# slim_bus_mixer_v1-4-layer.net
KiCad netlist of a schematic drawn in EAGLE
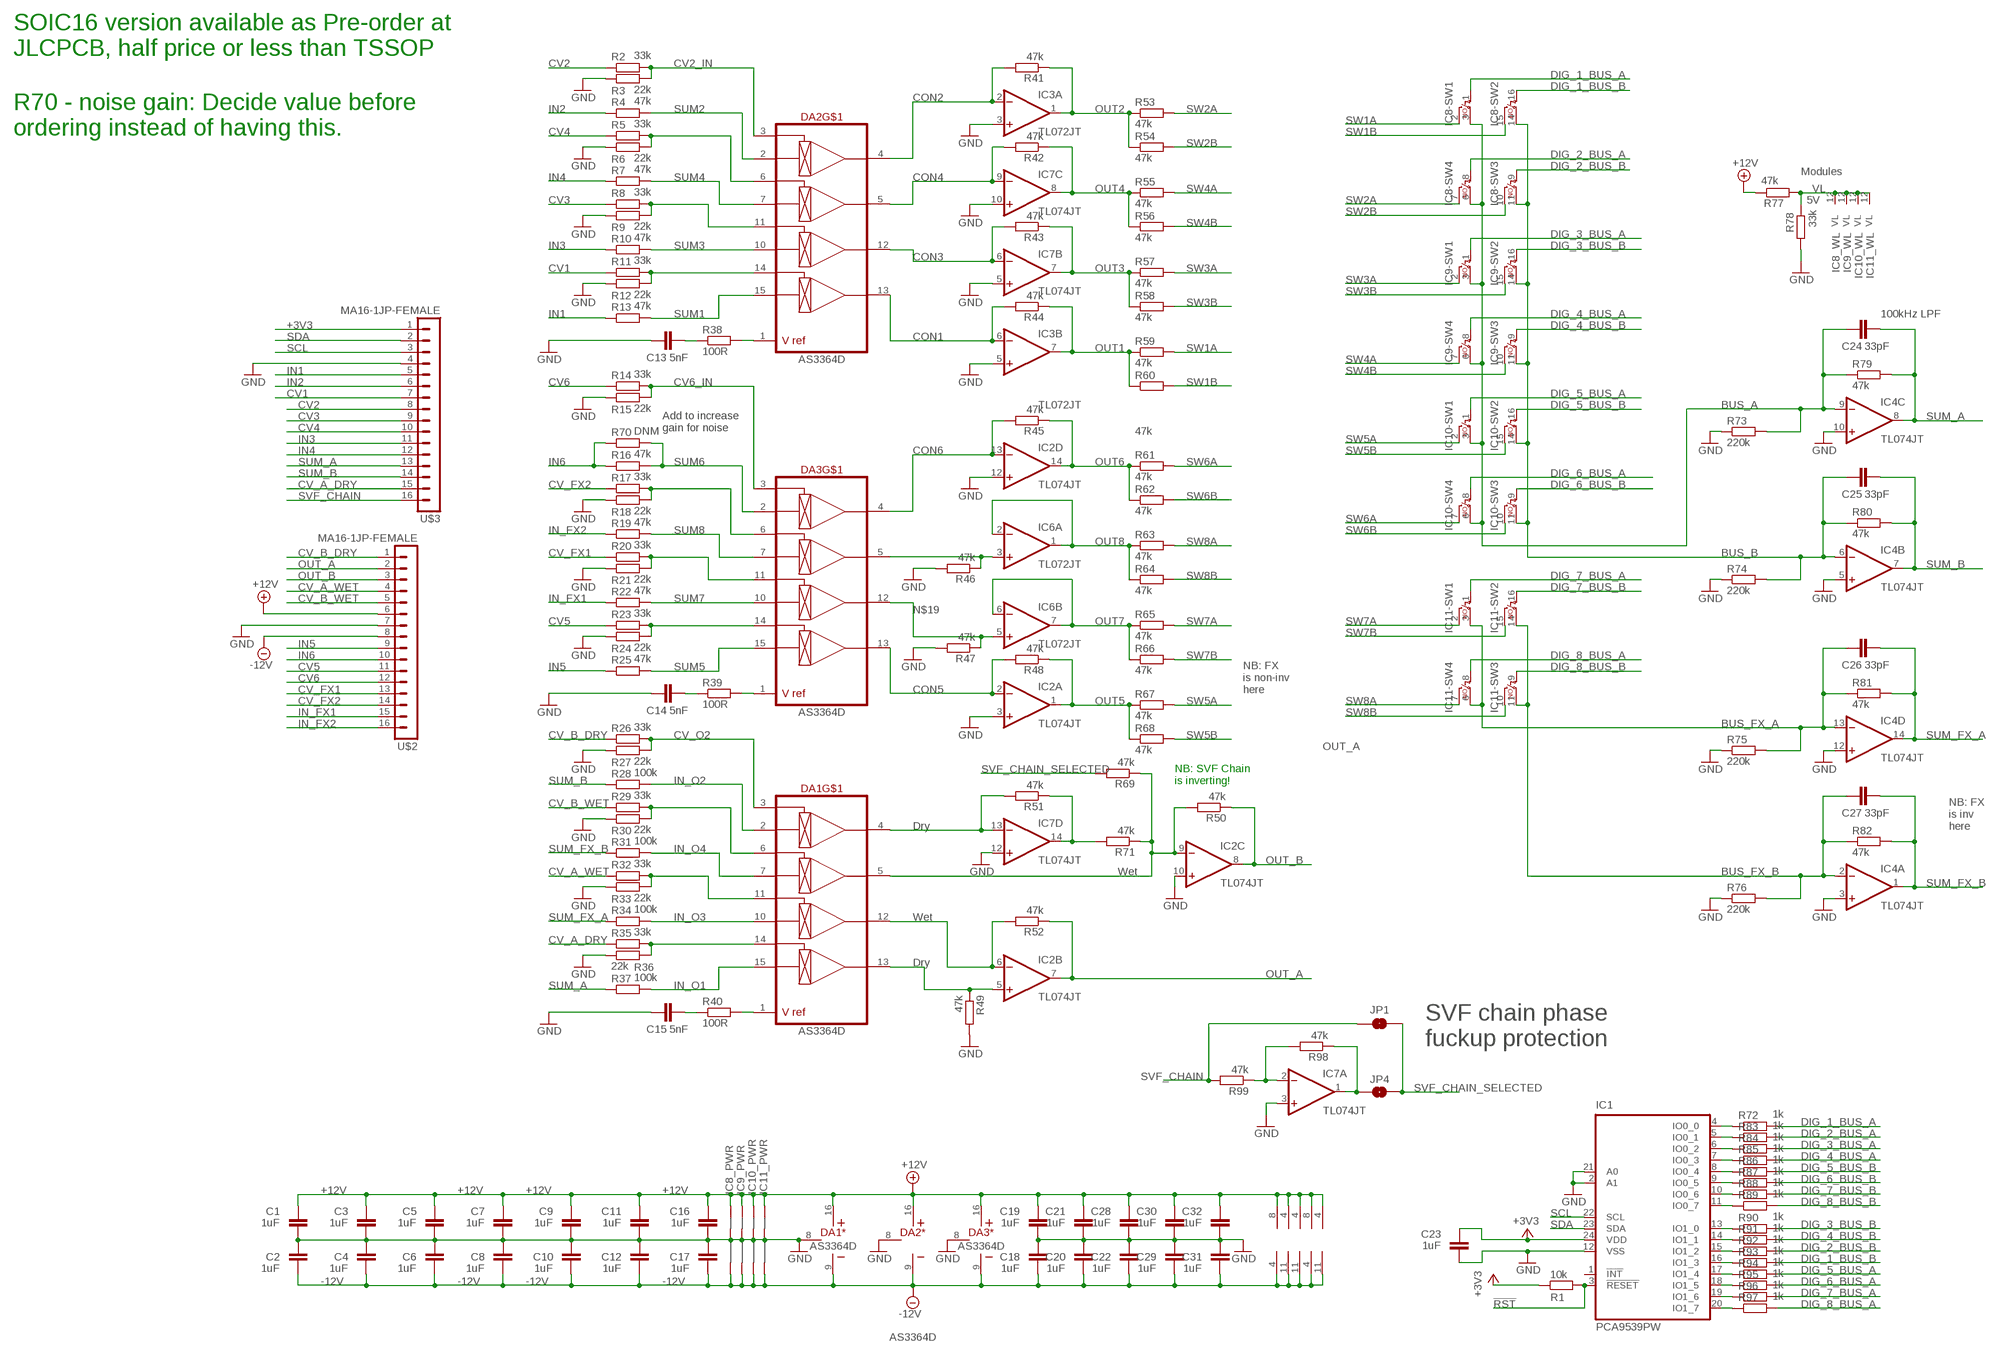
[diagram p0: schematic, sheet 1]

(export (version "E")
  (design (tool "Eeschema 10.0.6"))
  (components
    (comp (ref "C1")
      (value "1uF")
      (footprint "eagle-import:C0402-J")
      (libsource (lib "eagle-import") (part "C-EU-J0402"))
    )
    (comp (ref "C2")
      (value "1uF")
      (footprint "eagle-import:C0402-J")
      (libsource (lib "eagle-import") (part "C-EU-J0402"))
    )
    (comp (ref "C3")
      (value "1uF")
      (footprint "eagle-import:C0402-J")
      (libsource (lib "eagle-import") (part "C-EU-J0402"))
    )
    (comp (ref "C4")
      (value "1uF")
      (footprint "eagle-import:C0402-J")
      (libsource (lib "eagle-import") (part "C-EU-J0402"))
    )
    (comp (ref "C5")
      (value "1uF")
      (footprint "eagle-import:C0402-J")
      (libsource (lib "eagle-import") (part "C-EU-J0402"))
    )
    (comp (ref "C6")
      (value "1uF")
      (footprint "eagle-import:C0402-J")
      (libsource (lib "eagle-import") (part "C-EU-J0402"))
    )
    (comp (ref "C7")
      (value "1uF")
      (footprint "eagle-import:C0402-J")
      (libsource (lib "eagle-import") (part "C-EU-J0402"))
    )
    (comp (ref "C8")
      (value "1uF")
      (footprint "eagle-import:C0402-J")
      (libsource (lib "eagle-import") (part "C-EU-J0402"))
    )
    (comp (ref "C9")
      (value "1uF")
      (footprint "eagle-import:C0402-J")
      (libsource (lib "eagle-import") (part "C-EU-J0402"))
    )
    (comp (ref "C10")
      (value "1uF")
      (footprint "eagle-import:C0402-J")
      (libsource (lib "eagle-import") (part "C-EU-J0402"))
    )
    (comp (ref "C11")
      (value "1uF")
      (footprint "eagle-import:C0402-J")
      (libsource (lib "eagle-import") (part "C-EU-J0402"))
    )
    (comp (ref "C12")
      (value "1uF")
      (footprint "eagle-import:C0402-J")
      (libsource (lib "eagle-import") (part "C-EU-J0402"))
    )
    (comp (ref "C13")
      (value "5nF")
      (footprint "eagle-import:C0402-J")
      (libsource (lib "eagle-import") (part "C-EU-J0402"))
    )
    (comp (ref "C14")
      (value "5nF")
      (footprint "eagle-import:C0402-J")
      (libsource (lib "eagle-import") (part "C-EU-J0402"))
    )
    (comp (ref "C15")
      (value "5nF")
      (footprint "eagle-import:C0402-J")
      (libsource (lib "eagle-import") (part "C-EU-J0402"))
    )
    (comp (ref "C16")
      (value "1uF")
      (footprint "eagle-import:C0402-J")
      (libsource (lib "eagle-import") (part "C-EU-J0402"))
    )
    (comp (ref "C17")
      (value "1uF")
      (footprint "eagle-import:C0402-J")
      (libsource (lib "eagle-import") (part "C-EU-J0402"))
    )
    (comp (ref "C18")
      (value "1uF")
      (footprint "eagle-import:C0402-J")
      (libsource (lib "eagle-import") (part "C-EU-J0402"))
    )
    (comp (ref "C19")
      (value "1uF")
      (footprint "eagle-import:C0402-J")
      (libsource (lib "eagle-import") (part "C-EU-J0402"))
    )
    (comp (ref "C20")
      (value "1uF")
      (footprint "eagle-import:C0402-J")
      (libsource (lib "eagle-import") (part "C-EU-J0402"))
    )
    (comp (ref "C21")
      (value "1uF")
      (footprint "eagle-import:C0402-J")
      (libsource (lib "eagle-import") (part "C-EU-J0402"))
    )
    (comp (ref "C22")
      (value "1uF")
      (footprint "eagle-import:C0402-J")
      (libsource (lib "eagle-import") (part "C-EU-J0402"))
    )
    (comp (ref "C23")
      (value "1uF")
      (footprint "eagle-import:C0402-J")
      (libsource (lib "eagle-import") (part "C-EU-J0402"))
    )
    (comp (ref "C24")
      (value "33pF")
      (footprint "eagle-import:C0402-J")
      (libsource (lib "eagle-import") (part "C-EU-J0402"))
    )
    (comp (ref "C25")
      (value "33pF")
      (footprint "eagle-import:C0402-J")
      (libsource (lib "eagle-import") (part "C-EU-J0402"))
    )
    (comp (ref "C26")
      (value "33pF")
      (footprint "eagle-import:C0402-J")
      (libsource (lib "eagle-import") (part "C-EU-J0402"))
    )
    (comp (ref "C27")
      (value "33pF")
      (footprint "eagle-import:C0402-J")
      (libsource (lib "eagle-import") (part "C-EU-J0402"))
    )
    (comp (ref "C28")
      (value "1uF")
      (footprint "eagle-import:C0402-J")
      (libsource (lib "eagle-import") (part "C-EU-J0402"))
    )
    (comp (ref "C29")
      (value "1uF")
      (footprint "eagle-import:C0402-J")
      (libsource (lib "eagle-import") (part "C-EU-J0402"))
    )
    (comp (ref "C30")
      (value "1uF")
      (footprint "eagle-import:C0402-J")
      (libsource (lib "eagle-import") (part "C-EU-J0402"))
    )
    (comp (ref "C31")
      (value "1uF")
      (footprint "eagle-import:C0402-J")
      (libsource (lib "eagle-import") (part "C-EU-J0402"))
    )
    (comp (ref "C32")
      (value "1uF")
      (footprint "eagle-import:C0402-J")
      (libsource (lib "eagle-import") (part "C-EU-J0402"))
    )
    (comp (ref "DA1")
      (value "AS3364D")
      (footprint "eagle-import:DIL16J")
      (libsource (lib "eagle-import") (part "AS3364D"))
    )
    (comp (ref "DA2")
      (value "AS3364D")
      (footprint "eagle-import:DIL16J")
      (libsource (lib "eagle-import") (part "AS3364D"))
    )
    (comp (ref "DA3")
      (value "AS3364D")
      (footprint "eagle-import:DIL16J")
      (libsource (lib "eagle-import") (part "AS3364D"))
    )
    (comp (ref "IC1")
      (value "PCA9539PW")
      (footprint "eagle-import:TSSOP24J")
      (libsource (lib "eagle-import") (part "PCA9539PW"))
    )
    (comp (ref "IC2")
      (value "TL074JT")
      (footprint "eagle-import:TSSOP14J")
      (libsource (lib "eagle-import") (part "TL074JT"))
    )
    (comp (ref "IC3")
      (value "TL072JT")
      (footprint "eagle-import:TSSOP8J")
      (libsource (lib "eagle-import") (part "TL072JT"))
    )
    (comp (ref "IC4")
      (value "TL074JT")
      (footprint "eagle-import:TSSOP14J")
      (libsource (lib "eagle-import") (part "TL074JT"))
    )
    (comp (ref "IC6")
      (value "TL072JT")
      (footprint "eagle-import:TSSOP8J")
      (libsource (lib "eagle-import") (part "TL072JT"))
    )
    (comp (ref "IC7")
      (value "TL074JT")
      (footprint "eagle-import:TSSOP14J")
      (libsource (lib "eagle-import") (part "TL074JT"))
    )
    (comp (ref "IC8")
      (value "DG412-JS")
      (footprint "eagle-import:SO-16")
      (libsource (lib "eagle-import") (part "DG412-JS"))
    )
    (comp (ref "IC9")
      (value "DG412-JS")
      (footprint "eagle-import:SO-16")
      (libsource (lib "eagle-import") (part "DG412-JS"))
    )
    (comp (ref "IC10")
      (value "DG412-JS")
      (footprint "eagle-import:SO-16")
      (libsource (lib "eagle-import") (part "DG412-JS"))
    )
    (comp (ref "IC11")
      (value "DG412-JS")
      (footprint "eagle-import:SO-16")
      (libsource (lib "eagle-import") (part "DG412-JS"))
    )
    (comp (ref "JP1")
      (value "JUMPER-SMT_2_NC_TRACE_SILK-DNM")
      (footprint "eagle-import:SMT-JUMPER_2_NC_TRACE_SILK")
      (libsource (lib "eagle-import") (part "JUMPER-SMT_2_NC_TRACE_SILK"))
    )
    (comp (ref "JP4")
      (value "JUMPER-SMT_2_NO_SILK-DNM")
      (footprint "eagle-import:SMT-JUMPER_2_NO_SILK")
      (libsource (lib "eagle-import") (part "JUMPER-SMT_2_NO_SILK"))
    )
    (comp (ref "R1")
      (value "10k")
      (footprint "eagle-import:R0402")
      (libsource (lib "eagle-import") (part "R-EU_R0402"))
    )
    (comp (ref "R2")
      (value "33k")
      (footprint "eagle-import:R0402")
      (libsource (lib "eagle-import") (part "R-EU_R0402"))
    )
    (comp (ref "R3")
      (value "22k")
      (footprint "eagle-import:R0402")
      (libsource (lib "eagle-import") (part "R-EU_R0402"))
    )
    (comp (ref "R4")
      (value "47k")
      (footprint "eagle-import:R0402")
      (libsource (lib "eagle-import") (part "R-EU_R0402"))
    )
    (comp (ref "R5")
      (value "33k")
      (footprint "eagle-import:R0402")
      (libsource (lib "eagle-import") (part "R-EU_R0402"))
    )
    (comp (ref "R6")
      (value "22k")
      (footprint "eagle-import:R0402")
      (libsource (lib "eagle-import") (part "R-EU_R0402"))
    )
    (comp (ref "R7")
      (value "47k")
      (footprint "eagle-import:R0402")
      (libsource (lib "eagle-import") (part "R-EU_R0402"))
    )
    (comp (ref "R8")
      (value "33k")
      (footprint "eagle-import:R0402")
      (libsource (lib "eagle-import") (part "R-EU_R0402"))
    )
    (comp (ref "R9")
      (value "22k")
      (footprint "eagle-import:R0402")
      (libsource (lib "eagle-import") (part "R-EU_R0402"))
    )
    (comp (ref "R10")
      (value "47k")
      (footprint "eagle-import:R0402")
      (libsource (lib "eagle-import") (part "R-EU_R0402"))
    )
    (comp (ref "R11")
      (value "33k")
      (footprint "eagle-import:R0402")
      (libsource (lib "eagle-import") (part "R-EU_R0402"))
    )
    (comp (ref "R12")
      (value "22k")
      (footprint "eagle-import:R0402")
      (libsource (lib "eagle-import") (part "R-EU_R0402"))
    )
    (comp (ref "R13")
      (value "47k")
      (footprint "eagle-import:R0402")
      (libsource (lib "eagle-import") (part "R-EU_R0402"))
    )
    (comp (ref "R14")
      (value "33k")
      (footprint "eagle-import:R0402")
      (libsource (lib "eagle-import") (part "R-EU_R0402"))
    )
    (comp (ref "R15")
      (value "22k")
      (footprint "eagle-import:R0402")
      (libsource (lib "eagle-import") (part "R-EU_R0402"))
    )
    (comp (ref "R16")
      (value "47k")
      (footprint "eagle-import:R0402")
      (libsource (lib "eagle-import") (part "R-EU_R0402"))
    )
    (comp (ref "R17")
      (value "33k")
      (footprint "eagle-import:R0402")
      (libsource (lib "eagle-import") (part "R-EU_R0402"))
    )
    (comp (ref "R18")
      (value "22k")
      (footprint "eagle-import:R0402")
      (libsource (lib "eagle-import") (part "R-EU_R0402"))
    )
    (comp (ref "R19")
      (value "47k")
      (footprint "eagle-import:R0402")
      (libsource (lib "eagle-import") (part "R-EU_R0402"))
    )
    (comp (ref "R20")
      (value "33k")
      (footprint "eagle-import:R0402")
      (libsource (lib "eagle-import") (part "R-EU_R0402"))
    )
    (comp (ref "R21")
      (value "22k")
      (footprint "eagle-import:R0402")
      (libsource (lib "eagle-import") (part "R-EU_R0402"))
    )
    (comp (ref "R22")
      (value "47k")
      (footprint "eagle-import:R0402")
      (libsource (lib "eagle-import") (part "R-EU_R0402"))
    )
    (comp (ref "R23")
      (value "33k")
      (footprint "eagle-import:R0402")
      (libsource (lib "eagle-import") (part "R-EU_R0402"))
    )
    (comp (ref "R24")
      (value "22k")
      (footprint "eagle-import:R0402")
      (libsource (lib "eagle-import") (part "R-EU_R0402"))
    )
    (comp (ref "R25")
      (value "47k")
      (footprint "eagle-import:R0402")
      (libsource (lib "eagle-import") (part "R-EU_R0402"))
    )
    (comp (ref "R26")
      (value "33k")
      (footprint "eagle-import:R0402")
      (libsource (lib "eagle-import") (part "R-EU_R0402"))
    )
    (comp (ref "R27")
      (value "22k")
      (footprint "eagle-import:R0402")
      (libsource (lib "eagle-import") (part "R-EU_R0402"))
    )
    (comp (ref "R28")
      (value "100k")
      (footprint "eagle-import:R0402")
      (libsource (lib "eagle-import") (part "R-EU_R0402"))
    )
    (comp (ref "R29")
      (value "33k")
      (footprint "eagle-import:R0402")
      (libsource (lib "eagle-import") (part "R-EU_R0402"))
    )
    (comp (ref "R30")
      (value "22k")
      (footprint "eagle-import:R0402")
      (libsource (lib "eagle-import") (part "R-EU_R0402"))
    )
    (comp (ref "R31")
      (value "100k")
      (footprint "eagle-import:R0402")
      (libsource (lib "eagle-import") (part "R-EU_R0402"))
    )
    (comp (ref "R32")
      (value "33k")
      (footprint "eagle-import:R0402")
      (libsource (lib "eagle-import") (part "R-EU_R0402"))
    )
    (comp (ref "R33")
      (value "22k")
      (footprint "eagle-import:R0402")
      (libsource (lib "eagle-import") (part "R-EU_R0402"))
    )
    (comp (ref "R34")
      (value "100k")
      (footprint "eagle-import:R0402")
      (libsource (lib "eagle-import") (part "R-EU_R0402"))
    )
    (comp (ref "R35")
      (value "33k")
      (footprint "eagle-import:R0402")
      (libsource (lib "eagle-import") (part "R-EU_R0402"))
    )
    (comp (ref "R36")
      (value "22k")
      (footprint "eagle-import:R0402")
      (libsource (lib "eagle-import") (part "R-EU_R0402"))
    )
    (comp (ref "R37")
      (value "100k")
      (footprint "eagle-import:R0402")
      (libsource (lib "eagle-import") (part "R-EU_R0402"))
    )
    (comp (ref "R38")
      (value "100R")
      (footprint "eagle-import:R0402")
      (libsource (lib "eagle-import") (part "R-EU_R0402"))
    )
    (comp (ref "R39")
      (value "100R")
      (footprint "eagle-import:R0402")
      (libsource (lib "eagle-import") (part "R-EU_R0402"))
    )
    (comp (ref "R40")
      (value "100R")
      (footprint "eagle-import:R0402")
      (libsource (lib "eagle-import") (part "R-EU_R0402"))
    )
    (comp (ref "R41")
      (value "47k")
      (footprint "eagle-import:R0402")
      (libsource (lib "eagle-import") (part "R-EU_R0402"))
    )
    (comp (ref "R42")
      (value "47k")
      (footprint "eagle-import:R0402")
      (libsource (lib "eagle-import") (part "R-EU_R0402"))
    )
    (comp (ref "R43")
      (value "47k")
      (footprint "eagle-import:R0402")
      (libsource (lib "eagle-import") (part "R-EU_R0402"))
    )
    (comp (ref "R44")
      (value "47k")
      (footprint "eagle-import:R0402")
      (libsource (lib "eagle-import") (part "R-EU_R0402"))
    )
    (comp (ref "R45")
      (value "47k")
      (footprint "eagle-import:R0402")
      (libsource (lib "eagle-import") (part "R-EU_R0402"))
    )
    (comp (ref "R46")
      (value "47k")
      (footprint "eagle-import:R0402")
      (libsource (lib "eagle-import") (part "R-EU_R0402"))
    )
    (comp (ref "R47")
      (value "47k")
      (footprint "eagle-import:R0402")
      (libsource (lib "eagle-import") (part "R-EU_R0402"))
    )
    (comp (ref "R48")
      (value "47k")
      (footprint "eagle-import:R0402")
      (libsource (lib "eagle-import") (part "R-EU_R0402"))
    )
    (comp (ref "R49")
      (value "47k")
      (footprint "eagle-import:R0402")
      (libsource (lib "eagle-import") (part "R-EU_R0402"))
    )
    (comp (ref "R50")
      (value "47k")
      (footprint "eagle-import:R0402")
      (libsource (lib "eagle-import") (part "R-EU_R0402"))
    )
    (comp (ref "R51")
      (value "47k")
      (footprint "eagle-import:R0402")
      (libsource (lib "eagle-import") (part "R-EU_R0402"))
    )
    (comp (ref "R52")
      (value "47k")
      (footprint "eagle-import:R0402")
      (libsource (lib "eagle-import") (part "R-EU_R0402"))
    )
    (comp (ref "R53")
      (value "47k")
      (footprint "eagle-import:R0402")
      (libsource (lib "eagle-import") (part "R-EU_R0402"))
    )
    (comp (ref "R54")
      (value "47k")
      (footprint "eagle-import:R0402")
      (libsource (lib "eagle-import") (part "R-EU_R0402"))
    )
    (comp (ref "R55")
      (value "47k")
      (footprint "eagle-import:R0402")
      (libsource (lib "eagle-import") (part "R-EU_R0402"))
    )
    (comp (ref "R56")
      (value "47k")
      (footprint "eagle-import:R0402")
      (libsource (lib "eagle-import") (part "R-EU_R0402"))
    )
    (comp (ref "R57")
      (value "47k")
      (footprint "eagle-import:R0402")
      (libsource (lib "eagle-import") (part "R-EU_R0402"))
    )
    (comp (ref "R58")
      (value "47k")
      (footprint "eagle-import:R0402")
      (libsource (lib "eagle-import") (part "R-EU_R0402"))
    )
    (comp (ref "R59")
      (value "47k")
      (footprint "eagle-import:R0402")
      (libsource (lib "eagle-import") (part "R-EU_R0402"))
    )
    (comp (ref "R60")
      (value "47k")
      (footprint "eagle-import:R0402")
      (libsource (lib "eagle-import") (part "R-EU_R0402"))
    )
    (comp (ref "R61")
      (value "47k")
      (footprint "eagle-import:R0402")
      (libsource (lib "eagle-import") (part "R-EU_R0402"))
    )
    (comp (ref "R62")
      (value "47k")
      (footprint "eagle-import:R0402")
      (libsource (lib "eagle-import") (part "R-EU_R0402"))
    )
    (comp (ref "R63")
      (value "47k")
      (footprint "eagle-import:R0402")
      (libsource (lib "eagle-import") (part "R-EU_R0402"))
    )
    (comp (ref "R64")
      (value "47k")
      (footprint "eagle-import:R0402")
      (libsource (lib "eagle-import") (part "R-EU_R0402"))
    )
    (comp (ref "R65")
      (value "47k")
      (footprint "eagle-import:R0402")
      (libsource (lib "eagle-import") (part "R-EU_R0402"))
    )
    (comp (ref "R66")
      (value "47k")
      (footprint "eagle-import:R0402")
      (libsource (lib "eagle-import") (part "R-EU_R0402"))
    )
    (comp (ref "R67")
      (value "47k")
      (footprint "eagle-import:R0402")
      (libsource (lib "eagle-import") (part "R-EU_R0402"))
    )
    (comp (ref "R68")
      (value "47k")
      (footprint "eagle-import:R0402")
      (libsource (lib "eagle-import") (part "R-EU_R0402"))
    )
    (comp (ref "R69")
      (value "47k")
      (footprint "eagle-import:R0402")
      (libsource (lib "eagle-import") (part "R-EU_R0402"))
    )
    (comp (ref "R70")
      (value "DNM")
      (footprint "eagle-import:R0805")
      (libsource (lib "eagle-import") (part "R-EU_R0805"))
    )
    (comp (ref "R71")
      (value "47k")
      (footprint "eagle-import:R0402")
      (libsource (lib "eagle-import") (part "R-EU_R0402"))
    )
    (comp (ref "R72")
      (value "1k")
      (footprint "eagle-import:R0402")
      (libsource (lib "eagle-import") (part "R-EU_R0402"))
    )
    (comp (ref "R73")
      (value "220k")
      (footprint "eagle-import:R0603")
      (libsource (lib "eagle-import") (part "R-EU_R0603"))
    )
    (comp (ref "R74")
      (value "220k")
      (footprint "eagle-import:R0603")
      (libsource (lib "eagle-import") (part "R-EU_R0603"))
    )
    (comp (ref "R75")
      (value "220k")
      (footprint "eagle-import:R0603")
      (libsource (lib "eagle-import") (part "R-EU_R0603"))
    )
    (comp (ref "R76")
      (value "220k")
      (footprint "eagle-import:R0603")
      (libsource (lib "eagle-import") (part "R-EU_R0603"))
    )
    (comp (ref "R77")
      (value "47k")
      (footprint "eagle-import:R0402")
      (libsource (lib "eagle-import") (part "R-EU_R0402"))
    )
    (comp (ref "R78")
      (value "33k")
      (footprint "eagle-import:R0402")
      (libsource (lib "eagle-import") (part "R-EU_R0402"))
    )
    (comp (ref "R79")
      (value "47k")
      (footprint "eagle-import:R0402")
      (libsource (lib "eagle-import") (part "R-EU_R0402"))
    )
    (comp (ref "R80")
      (value "47k")
      (footprint "eagle-import:R0402")
      (libsource (lib "eagle-import") (part "R-EU_R0402"))
    )
    (comp (ref "R81")
      (value "47k")
      (footprint "eagle-import:R0402")
      (libsource (lib "eagle-import") (part "R-EU_R0402"))
    )
    (comp (ref "R82")
      (value "47k")
      (footprint "eagle-import:R0402")
      (libsource (lib "eagle-import") (part "R-EU_R0402"))
    )
    (comp (ref "R83")
      (value "1k")
      (footprint "eagle-import:R0402")
      (libsource (lib "eagle-import") (part "R-EU_R0402"))
    )
    (comp (ref "R84")
      (value "1k")
      (footprint "eagle-import:R0402")
      (libsource (lib "eagle-import") (part "R-EU_R0402"))
    )
    (comp (ref "R85")
      (value "1k")
      (footprint "eagle-import:R0402")
      (libsource (lib "eagle-import") (part "R-EU_R0402"))
    )
    (comp (ref "R86")
      (value "1k")
      (footprint "eagle-import:R0402")
      (libsource (lib "eagle-import") (part "R-EU_R0402"))
    )
    (comp (ref "R87")
      (value "1k")
      (footprint "eagle-import:R0402")
      (libsource (lib "eagle-import") (part "R-EU_R0402"))
    )
    (comp (ref "R88")
      (value "1k")
      (footprint "eagle-import:R0402")
      (libsource (lib "eagle-import") (part "R-EU_R0402"))
    )
    (comp (ref "R89")
      (value "1k")
      (footprint "eagle-import:R0402")
      (libsource (lib "eagle-import") (part "R-EU_R0402"))
    )
    (comp (ref "R90")
      (value "1k")
      (footprint "eagle-import:R0402")
      (libsource (lib "eagle-import") (part "R-EU_R0402"))
    )
    (comp (ref "R91")
      (value "1k")
      (footprint "eagle-import:R0402")
      (libsource (lib "eagle-import") (part "R-EU_R0402"))
    )
    (comp (ref "R92")
      (value "1k")
      (footprint "eagle-import:R0402")
      (libsource (lib "eagle-import") (part "R-EU_R0402"))
    )
    (comp (ref "R93")
      (value "1k")
      (footprint "eagle-import:R0402")
      (libsource (lib "eagle-import") (part "R-EU_R0402"))
    )
    (comp (ref "R94")
      (value "1k")
      (footprint "eagle-import:R0402")
      (libsource (lib "eagle-import") (part "R-EU_R0402"))
    )
    (comp (ref "R95")
      (value "1k")
      (footprint "eagle-import:R0402")
      (libsource (lib "eagle-import") (part "R-EU_R0402"))
    )
    (comp (ref "R96")
      (value "1k")
      (footprint "eagle-import:R0402")
      (libsource (lib "eagle-import") (part "R-EU_R0402"))
    )
    (comp (ref "R97")
      (value "1k")
      (footprint "eagle-import:R0402")
      (libsource (lib "eagle-import") (part "R-EU_R0402"))
    )
    (comp (ref "R98")
      (value "47k")
      (footprint "eagle-import:R0402")
      (libsource (lib "eagle-import") (part "R-EU_R0402"))
    )
    (comp (ref "R99")
      (value "47k")
      (footprint "eagle-import:R0402")
      (libsource (lib "eagle-import") (part "R-EU_R0402"))
    )
    (comp (ref "U$2")
      (value "MA16-1JP-FEMALE")
      (footprint "eagle-import:SIP-PIN16-1J")
      (libsource (lib "eagle-import") (part "MA16-1JP"))
    )
    (comp (ref "U$3")
      (value "MA16-1JP-FEMALE")
      (footprint "eagle-import:SIP-PIN16-1J")
      (libsource (lib "eagle-import") (part "MA16-1JP"))
    )
  )
  (nets
    (net (code "1") (name "+3V3") (class "Default")
      (node (ref "C23") (pin "2") (pinfunction "2_2") (pintype "passive"))
      (node (ref "IC1") (pin "24") (pinfunction "VDD_24") (pintype "power_in"))
      (node (ref "R1") (pin "1") (pinfunction "1_1") (pintype "passive"))
      (node (ref "U$3") (pin "1") (pinfunction "1_1") (pintype "passive"))
    )
    (net (code "2") (name "+12V") (class "Default")
      (node (ref "C1") (pin "2") (pinfunction "2_2") (pintype "passive"))
      (node (ref "C11") (pin "2") (pinfunction "2_2") (pintype "passive"))
      (node (ref "C16") (pin "2") (pinfunction "2_2") (pintype "passive"))
      (node (ref "C19") (pin "2") (pinfunction "2_2") (pintype "passive"))
      (node (ref "C21") (pin "2") (pinfunction "2_2") (pintype "passive"))
      (node (ref "C28") (pin "2") (pinfunction "2_2") (pintype "passive"))
      (node (ref "C3") (pin "2") (pinfunction "2_2") (pintype "passive"))
      (node (ref "C30") (pin "2") (pinfunction "2_2") (pintype "passive"))
      (node (ref "C32") (pin "2") (pinfunction "2_2") (pintype "passive"))
      (node (ref "C5") (pin "2") (pinfunction "2_2") (pintype "passive"))
      (node (ref "C7") (pin "2") (pinfunction "2_2") (pintype "passive"))
      (node (ref "C9") (pin "2") (pinfunction "2_2") (pintype "passive"))
      (node (ref "DA1") (pin "16") (pinfunction "V+_16") (pintype "power_in"))
      (node (ref "DA2") (pin "16") (pinfunction "V+_16") (pintype "power_in"))
      (node (ref "DA3") (pin "16") (pinfunction "V+_16") (pintype "power_in"))
      (node (ref "IC10") (pin "13") (pinfunction "+15V_13") (pintype "power_in"))
      (node (ref "IC11") (pin "13") (pinfunction "+15V_13") (pintype "power_in"))
      (node (ref "IC2") (pin "4") (pinfunction "V+_4") (pintype "power_in"))
      (node (ref "IC3") (pin "8") (pinfunction "V+_8") (pintype "power_in"))
      (node (ref "IC4") (pin "4") (pinfunction "V+_4") (pintype "power_in"))
      (node (ref "IC6") (pin "8") (pinfunction "V+_8") (pintype "power_in"))
      (node (ref "IC7") (pin "4") (pinfunction "V+_4") (pintype "power_in"))
      (node (ref "IC8") (pin "13") (pinfunction "+15V_13") (pintype "power_in"))
      (node (ref "IC9") (pin "13") (pinfunction "+15V_13") (pintype "power_in"))
      (node (ref "R77") (pin "1") (pinfunction "1_1") (pintype "passive"))
      (node (ref "U$2") (pin "6") (pinfunction "6_6") (pintype "passive"))
    )
    (net (code "3") (name "-12V") (class "Default")
      (node (ref "C10") (pin "1") (pinfunction "1_1") (pintype "passive"))
      (node (ref "C12") (pin "1") (pinfunction "1_1") (pintype "passive"))
      (node (ref "C17") (pin "1") (pinfunction "1_1") (pintype "passive"))
      (node (ref "C18") (pin "1") (pinfunction "1_1") (pintype "passive"))
      (node (ref "C2") (pin "1") (pinfunction "1_1") (pintype "passive"))
      (node (ref "C20") (pin "1") (pinfunction "1_1") (pintype "passive"))
      (node (ref "C22") (pin "1") (pinfunction "1_1") (pintype "passive"))
      (node (ref "C29") (pin "1") (pinfunction "1_1") (pintype "passive"))
      (node (ref "C31") (pin "1") (pinfunction "1_1") (pintype "passive"))
      (node (ref "C4") (pin "1") (pinfunction "1_1") (pintype "passive"))
      (node (ref "C6") (pin "1") (pinfunction "1_1") (pintype "passive"))
      (node (ref "C8") (pin "1") (pinfunction "1_1") (pintype "passive"))
      (node (ref "DA1") (pin "9") (pinfunction "V-_9") (pintype "power_in"))
      (node (ref "DA2") (pin "9") (pinfunction "V-_9") (pintype "power_in"))
      (node (ref "DA3") (pin "9") (pinfunction "V-_9") (pintype "power_in"))
      (node (ref "IC10") (pin "4") (pinfunction "-15V_4") (pintype "power_in"))
      (node (ref "IC11") (pin "4") (pinfunction "-15V_4") (pintype "power_in"))
      (node (ref "IC2") (pin "11") (pinfunction "V-_11") (pintype "power_in"))
      (node (ref "IC3") (pin "4") (pinfunction "V-_4") (pintype "power_in"))
      (node (ref "IC4") (pin "11") (pinfunction "V-_11") (pintype "power_in"))
      (node (ref "IC6") (pin "4") (pinfunction "V-_4") (pintype "power_in"))
      (node (ref "IC7") (pin "11") (pinfunction "V-_11") (pintype "power_in"))
      (node (ref "IC8") (pin "4") (pinfunction "-15V_4") (pintype "power_in"))
      (node (ref "IC9") (pin "4") (pinfunction "-15V_4") (pintype "power_in"))
      (node (ref "U$2") (pin "8") (pinfunction "8_8") (pintype "passive"))
    )
    (net (code "4") (name "/BUS_A") (class "Default")
      (node (ref "C24") (pin "1") (pinfunction "1_1") (pintype "passive"))
      (node (ref "IC10") (pin "3") (pinfunction "S_3") (pintype "bidirectional"))
      (node (ref "IC10") (pin "6") (pinfunction "S_6") (pintype "bidirectional"))
      (node (ref "IC4") (pin "9") (pinfunction "-IN_9") (pintype "input"))
      (node (ref "IC8") (pin "3") (pinfunction "S_3") (pintype "bidirectional"))
      (node (ref "IC8") (pin "6") (pinfunction "S_6") (pintype "bidirectional"))
      (node (ref "IC9") (pin "3") (pinfunction "S_3") (pintype "bidirectional"))
      (node (ref "IC9") (pin "6") (pinfunction "S_6") (pintype "bidirectional"))
      (node (ref "R73") (pin "2") (pinfunction "2_2") (pintype "passive"))
      (node (ref "R79") (pin "1") (pinfunction "1_1") (pintype "passive"))
    )
    (net (code "5") (name "/BUS_B") (class "Default")
      (node (ref "C25") (pin "1") (pinfunction "1_1") (pintype "passive"))
      (node (ref "IC10") (pin "11") (pinfunction "S_11") (pintype "bidirectional"))
      (node (ref "IC10") (pin "14") (pinfunction "S_14") (pintype "bidirectional"))
      (node (ref "IC4") (pin "6") (pinfunction "-IN_6") (pintype "input"))
      (node (ref "IC8") (pin "11") (pinfunction "S_11") (pintype "bidirectional"))
      (node (ref "IC8") (pin "14") (pinfunction "S_14") (pintype "bidirectional"))
      (node (ref "IC9") (pin "11") (pinfunction "S_11") (pintype "bidirectional"))
      (node (ref "IC9") (pin "14") (pinfunction "S_14") (pintype "bidirectional"))
      (node (ref "R74") (pin "2") (pinfunction "2_2") (pintype "passive"))
      (node (ref "R80") (pin "1") (pinfunction "1_1") (pintype "passive"))
    )
    (net (code "6") (name "/BUS_FX_A") (class "Default")
      (node (ref "C26") (pin "1") (pinfunction "1_1") (pintype "passive"))
      (node (ref "IC11") (pin "3") (pinfunction "S_3") (pintype "bidirectional"))
      (node (ref "IC11") (pin "6") (pinfunction "S_6") (pintype "bidirectional"))
      (node (ref "IC4") (pin "13") (pinfunction "-IN_13") (pintype "input"))
      (node (ref "R75") (pin "2") (pinfunction "2_2") (pintype "passive"))
      (node (ref "R81") (pin "1") (pinfunction "1_1") (pintype "passive"))
    )
    (net (code "7") (name "/BUS_FX_B") (class "Default")
      (node (ref "C27") (pin "1") (pinfunction "1_1") (pintype "passive"))
      (node (ref "IC11") (pin "11") (pinfunction "S_11") (pintype "bidirectional"))
      (node (ref "IC11") (pin "14") (pinfunction "S_14") (pintype "bidirectional"))
      (node (ref "IC4") (pin "2") (pinfunction "-IN_2") (pintype "input"))
      (node (ref "R76") (pin "2") (pinfunction "2_2") (pintype "passive"))
      (node (ref "R82") (pin "1") (pinfunction "1_1") (pintype "passive"))
    )
    (net (code "8") (name "/CON1") (class "Default")
      (node (ref "DA2") (pin "13") (pinfunction "OUT4_13") (pintype "output"))
      (node (ref "IC3") (pin "6") (pinfunction "-IN_6") (pintype "input"))
      (node (ref "R44") (pin "2") (pinfunction "2_2") (pintype "passive"))
    )
    (net (code "9") (name "/CON2") (class "Default")
      (node (ref "DA2") (pin "4") (pinfunction "OUT1_4") (pintype "output"))
      (node (ref "IC3") (pin "2") (pinfunction "-IN_2") (pintype "input"))
      (node (ref "R41") (pin "2") (pinfunction "2_2") (pintype "passive"))
    )
    (net (code "10") (name "/CON3") (class "Default")
      (node (ref "DA2") (pin "12") (pinfunction "OUT3_12") (pintype "output"))
      (node (ref "IC7") (pin "6") (pinfunction "-IN_6") (pintype "input"))
      (node (ref "R43") (pin "2") (pinfunction "2_2") (pintype "passive"))
    )
    (net (code "11") (name "/CON4") (class "Default")
      (node (ref "DA2") (pin "5") (pinfunction "OUT2_5") (pintype "output"))
      (node (ref "IC7") (pin "9") (pinfunction "-IN_9") (pintype "input"))
      (node (ref "R42") (pin "2") (pinfunction "2_2") (pintype "passive"))
    )
    (net (code "12") (name "/CON5") (class "Default")
      (node (ref "DA3") (pin "13") (pinfunction "OUT4_13") (pintype "output"))
      (node (ref "IC2") (pin "2") (pinfunction "-IN_2") (pintype "input"))
      (node (ref "R48") (pin "2") (pinfunction "2_2") (pintype "passive"))
    )
    (net (code "13") (name "/CON6") (class "Default")
      (node (ref "DA3") (pin "4") (pinfunction "OUT1_4") (pintype "output"))
      (node (ref "IC2") (pin "13") (pinfunction "-IN_13") (pintype "input"))
      (node (ref "R45") (pin "2") (pinfunction "2_2") (pintype "passive"))
    )
    (net (code "14") (name "/CV1") (class "Default")
      (node (ref "R11") (pin "1") (pinfunction "1_1") (pintype "passive"))
      (node (ref "U$3") (pin "7") (pinfunction "7_7") (pintype "passive"))
    )
    (net (code "15") (name "/CV2") (class "Default")
      (node (ref "R2") (pin "1") (pinfunction "1_1") (pintype "passive"))
      (node (ref "U$3") (pin "8") (pinfunction "8_8") (pintype "passive"))
    )
    (net (code "16") (name "/CV2_IN") (class "Default")
      (node (ref "DA2") (pin "3") (pinfunction "CV1_3") (pintype "input"))
      (node (ref "R2") (pin "2") (pinfunction "2_2") (pintype "passive"))
      (node (ref "R3") (pin "2") (pinfunction "2_2") (pintype "passive"))
    )
    (net (code "17") (name "/CV3") (class "Default")
      (node (ref "R8") (pin "1") (pinfunction "1_1") (pintype "passive"))
      (node (ref "U$3") (pin "9") (pinfunction "9_9") (pintype "passive"))
    )
    (net (code "18") (name "/CV4") (class "Default")
      (node (ref "R5") (pin "1") (pinfunction "1_1") (pintype "passive"))
      (node (ref "U$3") (pin "10") (pinfunction "10_10") (pintype "passive"))
    )
    (net (code "19") (name "/CV5") (class "Default")
      (node (ref "R23") (pin "1") (pinfunction "1_1") (pintype "passive"))
      (node (ref "U$2") (pin "11") (pinfunction "11_11") (pintype "passive"))
    )
    (net (code "20") (name "/CV6") (class "Default")
      (node (ref "R14") (pin "1") (pinfunction "1_1") (pintype "passive"))
      (node (ref "U$2") (pin "12") (pinfunction "12_12") (pintype "passive"))
    )
    (net (code "21") (name "/CV6_IN") (class "Default")
      (node (ref "DA3") (pin "3") (pinfunction "CV1_3") (pintype "input"))
      (node (ref "R14") (pin "2") (pinfunction "2_2") (pintype "passive"))
      (node (ref "R15") (pin "2") (pinfunction "2_2") (pintype "passive"))
    )
    (net (code "22") (name "/CV_A_DRY") (class "Default")
      (node (ref "R35") (pin "1") (pinfunction "1_1") (pintype "passive"))
      (node (ref "U$3") (pin "15") (pinfunction "15_15") (pintype "passive"))
    )
    (net (code "23") (name "/CV_A_WET") (class "Default")
      (node (ref "R32") (pin "1") (pinfunction "1_1") (pintype "passive"))
      (node (ref "U$2") (pin "4") (pinfunction "4_4") (pintype "passive"))
    )
    (net (code "24") (name "/CV_B_DRY") (class "Default")
      (node (ref "R26") (pin "1") (pinfunction "1_1") (pintype "passive"))
      (node (ref "U$2") (pin "1") (pinfunction "1_1") (pintype "passive"))
    )
    (net (code "25") (name "/CV_B_WET") (class "Default")
      (node (ref "R29") (pin "1") (pinfunction "1_1") (pintype "passive"))
      (node (ref "U$2") (pin "5") (pinfunction "5_5") (pintype "passive"))
    )
    (net (code "26") (name "/CV_FX1") (class "Default")
      (node (ref "R20") (pin "1") (pinfunction "1_1") (pintype "passive"))
      (node (ref "U$2") (pin "13") (pinfunction "13_13") (pintype "passive"))
    )
    (net (code "27") (name "/CV_FX2") (class "Default")
      (node (ref "R17") (pin "1") (pinfunction "1_1") (pintype "passive"))
      (node (ref "U$2") (pin "14") (pinfunction "14_14") (pintype "passive"))
    )
    (net (code "28") (name "/CV_O2") (class "Default")
      (node (ref "DA1") (pin "3") (pinfunction "CV1_3") (pintype "input"))
      (node (ref "R26") (pin "2") (pinfunction "2_2") (pintype "passive"))
      (node (ref "R27") (pin "2") (pinfunction "2_2") (pintype "passive"))
    )
    (net (code "29") (name "/DIG_1_BUS_A") (class "Default")
      (node (ref "IC8") (pin "1") (pinfunction "C_1") (pintype "bidirectional"))
      (node (ref "R72") (pin "2") (pinfunction "2_2") (pintype "passive"))
    )
    (net (code "30") (name "/DIG_1_BUS_B") (class "Default")
      (node (ref "IC8") (pin "16") (pinfunction "C_16") (pintype "bidirectional"))
      (node (ref "R93") (pin "2") (pinfunction "2_2") (pintype "passive"))
    )
    (net (code "31") (name "/DIG_2_BUS_A") (class "Default")
      (node (ref "IC8") (pin "8") (pinfunction "C_8") (pintype "bidirectional"))
      (node (ref "R83") (pin "2") (pinfunction "2_2") (pintype "passive"))
    )
    (net (code "32") (name "/DIG_2_BUS_B") (class "Default")
      (node (ref "IC8") (pin "9") (pinfunction "C_9") (pintype "bidirectional"))
      (node (ref "R92") (pin "2") (pinfunction "2_2") (pintype "passive"))
    )
    (net (code "33") (name "/DIG_3_BUS_A") (class "Default")
      (node (ref "IC9") (pin "1") (pinfunction "C_1") (pintype "bidirectional"))
      (node (ref "R84") (pin "2") (pinfunction "2_2") (pintype "passive"))
    )
    (net (code "34") (name "/DIG_3_BUS_B") (class "Default")
      (node (ref "IC9") (pin "16") (pinfunction "C_16") (pintype "bidirectional"))
      (node (ref "R90") (pin "2") (pinfunction "2_2") (pintype "passive"))
    )
    (net (code "35") (name "/DIG_4_BUS_A") (class "Default")
      (node (ref "IC9") (pin "8") (pinfunction "C_8") (pintype "bidirectional"))
      (node (ref "R85") (pin "2") (pinfunction "2_2") (pintype "passive"))
    )
    (net (code "36") (name "/DIG_4_BUS_B") (class "Default")
      (node (ref "IC9") (pin "9") (pinfunction "C_9") (pintype "bidirectional"))
      (node (ref "R91") (pin "2") (pinfunction "2_2") (pintype "passive"))
    )
    (net (code "37") (name "/DIG_5_BUS_A") (class "Default")
      (node (ref "IC10") (pin "1") (pinfunction "C_1") (pintype "bidirectional"))
      (node (ref "R94") (pin "2") (pinfunction "2_2") (pintype "passive"))
    )
    (net (code "38") (name "/DIG_5_BUS_B") (class "Default")
      (node (ref "IC10") (pin "16") (pinfunction "C_16") (pintype "bidirectional"))
      (node (ref "R86") (pin "2") (pinfunction "2_2") (pintype "passive"))
    )
    (net (code "39") (name "/DIG_6_BUS_A") (class "Default")
      (node (ref "IC10") (pin "8") (pinfunction "C_8") (pintype "bidirectional"))
      (node (ref "R95") (pin "2") (pinfunction "2_2") (pintype "passive"))
    )
    (net (code "40") (name "/DIG_6_BUS_B") (class "Default")
      (node (ref "IC10") (pin "9") (pinfunction "C_9") (pintype "bidirectional"))
      (node (ref "R87") (pin "2") (pinfunction "2_2") (pintype "passive"))
    )
    (net (code "41") (name "/DIG_7_BUS_A") (class "Default")
      (node (ref "IC11") (pin "1") (pinfunction "C_1") (pintype "bidirectional"))
      (node (ref "R96") (pin "2") (pinfunction "2_2") (pintype "passive"))
    )
    (net (code "42") (name "/DIG_7_BUS_B") (class "Default")
      (node (ref "IC11") (pin "16") (pinfunction "C_16") (pintype "bidirectional"))
      (node (ref "R88") (pin "2") (pinfunction "2_2") (pintype "passive"))
    )
    (net (code "43") (name "/DIG_8_BUS_A") (class "Default")
      (node (ref "IC11") (pin "8") (pinfunction "C_8") (pintype "bidirectional"))
      (node (ref "R97") (pin "2") (pinfunction "2_2") (pintype "passive"))
    )
    (net (code "44") (name "/DIG_8_BUS_B") (class "Default")
      (node (ref "IC11") (pin "9") (pinfunction "C_9") (pintype "bidirectional"))
      (node (ref "R89") (pin "2") (pinfunction "2_2") (pintype "passive"))
    )
    (net (code "45") (name "/IN1") (class "Default")
      (node (ref "R13") (pin "1") (pinfunction "1_1") (pintype "passive"))
      (node (ref "U$3") (pin "5") (pinfunction "5_5") (pintype "passive"))
    )
    (net (code "46") (name "/IN2") (class "Default")
      (node (ref "R4") (pin "1") (pinfunction "1_1") (pintype "passive"))
      (node (ref "U$3") (pin "6") (pinfunction "6_6") (pintype "passive"))
    )
    (net (code "47") (name "/IN3") (class "Default")
      (node (ref "R10") (pin "1") (pinfunction "1_1") (pintype "passive"))
      (node (ref "U$3") (pin "11") (pinfunction "11_11") (pintype "passive"))
    )
    (net (code "48") (name "/IN4") (class "Default")
      (node (ref "R7") (pin "1") (pinfunction "1_1") (pintype "passive"))
      (node (ref "U$3") (pin "12") (pinfunction "12_12") (pintype "passive"))
    )
    (net (code "49") (name "/IN5") (class "Default")
      (node (ref "R25") (pin "1") (pinfunction "1_1") (pintype "passive"))
      (node (ref "U$2") (pin "9") (pinfunction "9_9") (pintype "passive"))
    )
    (net (code "50") (name "/IN6") (class "Default")
      (node (ref "R16") (pin "1") (pinfunction "1_1") (pintype "passive"))
      (node (ref "R70") (pin "1") (pinfunction "1_1") (pintype "passive"))
      (node (ref "U$2") (pin "10") (pinfunction "10_10") (pintype "passive"))
    )
    (net (code "51") (name "/IN_FX1") (class "Default")
      (node (ref "R22") (pin "1") (pinfunction "1_1") (pintype "passive"))
      (node (ref "U$2") (pin "15") (pinfunction "15_15") (pintype "passive"))
    )
    (net (code "52") (name "/IN_FX2") (class "Default")
      (node (ref "R19") (pin "1") (pinfunction "1_1") (pintype "passive"))
      (node (ref "U$2") (pin "16") (pinfunction "16_16") (pintype "passive"))
    )
    (net (code "53") (name "/IN_O1") (class "Default")
      (node (ref "DA1") (pin "15") (pinfunction "IN4_15") (pintype "input"))
      (node (ref "R37") (pin "2") (pinfunction "2_2") (pintype "passive"))
    )
    (net (code "54") (name "/IN_O2") (class "Default")
      (node (ref "DA1") (pin "2") (pinfunction "IN1_2") (pintype "input"))
      (node (ref "R28") (pin "2") (pinfunction "2_2") (pintype "passive"))
    )
    (net (code "55") (name "/IN_O3") (class "Default")
      (node (ref "DA1") (pin "10") (pinfunction "IN3_10") (pintype "input"))
      (node (ref "R34") (pin "2") (pinfunction "2_2") (pintype "passive"))
    )
    (net (code "56") (name "/IN_O4") (class "Default")
      (node (ref "DA1") (pin "7") (pinfunction "IN2_7") (pintype "input"))
      (node (ref "R31") (pin "2") (pinfunction "2_2") (pintype "passive"))
    )
    (net (code "57") (name "/N$19") (class "Default")
      (node (ref "DA3") (pin "12") (pinfunction "OUT3_12") (pintype "output"))
      (node (ref "IC6") (pin "5") (pinfunction "+IN_5") (pintype "input"))
      (node (ref "R47") (pin "1") (pinfunction "1_1") (pintype "passive"))
    )
    (net (code "58") (name "/OUT1") (class "Default")
      (node (ref "IC3") (pin "7") (pinfunction "OUT_7") (pintype "output"))
      (node (ref "R44") (pin "1") (pinfunction "1_1") (pintype "passive"))
      (node (ref "R59") (pin "1") (pinfunction "1_1") (pintype "passive"))
      (node (ref "R60") (pin "1") (pinfunction "1_1") (pintype "passive"))
    )
    (net (code "59") (name "/OUT2") (class "Default")
      (node (ref "IC3") (pin "1") (pinfunction "OUT_1") (pintype "output"))
      (node (ref "R41") (pin "1") (pinfunction "1_1") (pintype "passive"))
      (node (ref "R53") (pin "1") (pinfunction "1_1") (pintype "passive"))
      (node (ref "R54") (pin "1") (pinfunction "1_1") (pintype "passive"))
    )
    (net (code "60") (name "/OUT3") (class "Default")
      (node (ref "IC7") (pin "7") (pinfunction "OUT_7") (pintype "output"))
      (node (ref "R43") (pin "1") (pinfunction "1_1") (pintype "passive"))
      (node (ref "R57") (pin "1") (pinfunction "1_1") (pintype "passive"))
      (node (ref "R58") (pin "1") (pinfunction "1_1") (pintype "passive"))
    )
    (net (code "61") (name "/OUT4") (class "Default")
      (node (ref "IC7") (pin "8") (pinfunction "OUT_8") (pintype "output"))
      (node (ref "R42") (pin "1") (pinfunction "1_1") (pintype "passive"))
      (node (ref "R55") (pin "1") (pinfunction "1_1") (pintype "passive"))
      (node (ref "R56") (pin "1") (pinfunction "1_1") (pintype "passive"))
    )
    (net (code "62") (name "/OUT5") (class "Default")
      (node (ref "IC2") (pin "1") (pinfunction "OUT_1") (pintype "output"))
      (node (ref "R48") (pin "1") (pinfunction "1_1") (pintype "passive"))
      (node (ref "R67") (pin "1") (pinfunction "1_1") (pintype "passive"))
      (node (ref "R68") (pin "1") (pinfunction "1_1") (pintype "passive"))
    )
    (net (code "63") (name "/OUT6") (class "Default")
      (node (ref "IC2") (pin "14") (pinfunction "OUT_14") (pintype "output"))
      (node (ref "R45") (pin "1") (pinfunction "1_1") (pintype "passive"))
      (node (ref "R61") (pin "1") (pinfunction "1_1") (pintype "passive"))
      (node (ref "R62") (pin "1") (pinfunction "1_1") (pintype "passive"))
    )
    (net (code "64") (name "/OUT7") (class "Default")
      (node (ref "IC6") (pin "6") (pinfunction "-IN_6") (pintype "input"))
      (node (ref "IC6") (pin "7") (pinfunction "OUT_7") (pintype "output"))
      (node (ref "R65") (pin "1") (pinfunction "1_1") (pintype "passive"))
      (node (ref "R66") (pin "1") (pinfunction "1_1") (pintype "passive"))
    )
    (net (code "65") (name "/OUT8") (class "Default")
      (node (ref "IC6") (pin "1") (pinfunction "OUT_1") (pintype "output"))
      (node (ref "IC6") (pin "2") (pinfunction "-IN_2") (pintype "input"))
      (node (ref "R63") (pin "1") (pinfunction "1_1") (pintype "passive"))
      (node (ref "R64") (pin "1") (pinfunction "1_1") (pintype "passive"))
    )
    (net (code "66") (name "/OUT_A") (class "Default")
      (node (ref "IC2") (pin "7") (pinfunction "OUT_7") (pintype "output"))
      (node (ref "R52") (pin "1") (pinfunction "1_1") (pintype "passive"))
      (node (ref "U$2") (pin "2") (pinfunction "2_2") (pintype "passive"))
    )
    (net (code "67") (name "/OUT_B") (class "Default")
      (node (ref "IC2") (pin "8") (pinfunction "OUT_8") (pintype "output"))
      (node (ref "R50") (pin "1") (pinfunction "1_1") (pintype "passive"))
      (node (ref "U$2") (pin "3") (pinfunction "3_3") (pintype "passive"))
    )
    (net (code "68") (name "/SCL") (class "Default")
      (node (ref "IC1") (pin "22") (pinfunction "SCL_22") (pintype "bidirectional"))
      (node (ref "U$3") (pin "3") (pinfunction "3_3") (pintype "passive"))
    )
    (net (code "69") (name "/SDA") (class "Default")
      (node (ref "IC1") (pin "23") (pinfunction "SDA_23") (pintype "bidirectional"))
      (node (ref "U$3") (pin "2") (pinfunction "2_2") (pintype "passive"))
    )
    (net (code "70") (name "/SUM1") (class "Default")
      (node (ref "DA2") (pin "15") (pinfunction "IN4_15") (pintype "input"))
      (node (ref "R13") (pin "2") (pinfunction "2_2") (pintype "passive"))
    )
    (net (code "71") (name "/SUM2") (class "Default")
      (node (ref "DA2") (pin "2") (pinfunction "IN1_2") (pintype "input"))
      (node (ref "R4") (pin "2") (pinfunction "2_2") (pintype "passive"))
    )
    (net (code "72") (name "/SUM3") (class "Default")
      (node (ref "DA2") (pin "10") (pinfunction "IN3_10") (pintype "input"))
      (node (ref "R10") (pin "2") (pinfunction "2_2") (pintype "passive"))
    )
    (net (code "73") (name "/SUM4") (class "Default")
      (node (ref "DA2") (pin "7") (pinfunction "IN2_7") (pintype "input"))
      (node (ref "R7") (pin "2") (pinfunction "2_2") (pintype "passive"))
    )
    (net (code "74") (name "/SUM5") (class "Default")
      (node (ref "DA3") (pin "15") (pinfunction "IN4_15") (pintype "input"))
      (node (ref "R25") (pin "2") (pinfunction "2_2") (pintype "passive"))
    )
    (net (code "75") (name "/SUM6") (class "Default")
      (node (ref "DA3") (pin "2") (pinfunction "IN1_2") (pintype "input"))
      (node (ref "R16") (pin "2") (pinfunction "2_2") (pintype "passive"))
      (node (ref "R70") (pin "2") (pinfunction "2_2") (pintype "passive"))
    )
    (net (code "76") (name "/SUM7") (class "Default")
      (node (ref "DA3") (pin "10") (pinfunction "IN3_10") (pintype "input"))
      (node (ref "R22") (pin "2") (pinfunction "2_2") (pintype "passive"))
    )
    (net (code "77") (name "/SUM8") (class "Default")
      (node (ref "DA3") (pin "7") (pinfunction "IN2_7") (pintype "input"))
      (node (ref "R19") (pin "2") (pinfunction "2_2") (pintype "passive"))
    )
    (net (code "78") (name "/SUM_A") (class "Default")
      (node (ref "C24") (pin "2") (pinfunction "2_2") (pintype "passive"))
      (node (ref "IC4") (pin "8") (pinfunction "OUT_8") (pintype "output"))
      (node (ref "R37") (pin "1") (pinfunction "1_1") (pintype "passive"))
      (node (ref "R79") (pin "2") (pinfunction "2_2") (pintype "passive"))
      (node (ref "U$3") (pin "13") (pinfunction "13_13") (pintype "passive"))
    )
    (net (code "79") (name "/SUM_B") (class "Default")
      (node (ref "C25") (pin "2") (pinfunction "2_2") (pintype "passive"))
      (node (ref "IC4") (pin "7") (pinfunction "OUT_7") (pintype "output"))
      (node (ref "R28") (pin "1") (pinfunction "1_1") (pintype "passive"))
      (node (ref "R80") (pin "2") (pinfunction "2_2") (pintype "passive"))
      (node (ref "U$3") (pin "14") (pinfunction "14_14") (pintype "passive"))
    )
    (net (code "80") (name "/SUM_FX_A") (class "Default")
      (node (ref "C26") (pin "2") (pinfunction "2_2") (pintype "passive"))
      (node (ref "IC4") (pin "14") (pinfunction "OUT_14") (pintype "output"))
      (node (ref "R34") (pin "1") (pinfunction "1_1") (pintype "passive"))
      (node (ref "R81") (pin "2") (pinfunction "2_2") (pintype "passive"))
    )
    (net (code "81") (name "/SUM_FX_B") (class "Default")
      (node (ref "C27") (pin "2") (pinfunction "2_2") (pintype "passive"))
      (node (ref "IC4") (pin "1") (pinfunction "OUT_1") (pintype "output"))
      (node (ref "R31") (pin "1") (pinfunction "1_1") (pintype "passive"))
      (node (ref "R82") (pin "2") (pinfunction "2_2") (pintype "passive"))
    )
    (net (code "82") (name "/SVF_CHAIN") (class "Default")
      (node (ref "JP1") (pin "1") (pinfunction "1_1") (pintype "passive"))
      (node (ref "R99") (pin "2") (pinfunction "2_2") (pintype "passive"))
      (node (ref "U$3") (pin "16") (pinfunction "16_16") (pintype "passive"))
    )
    (net (code "83") (name "/SVF_CHAIN_SELECTED") (class "Default")
      (node (ref "JP1") (pin "2") (pinfunction "2_2") (pintype "passive"))
      (node (ref "JP4") (pin "2") (pinfunction "2_2") (pintype "passive"))
      (node (ref "R69") (pin "2") (pinfunction "2_2") (pintype "passive"))
    )
    (net (code "84") (name "/SW1A") (class "Default")
      (node (ref "IC8") (pin "2") (pinfunction "D_2") (pintype "bidirectional"))
      (node (ref "R59") (pin "2") (pinfunction "2_2") (pintype "passive"))
    )
    (net (code "85") (name "/SW1B") (class "Default")
      (node (ref "IC8") (pin "15") (pinfunction "D_15") (pintype "bidirectional"))
      (node (ref "R60") (pin "2") (pinfunction "2_2") (pintype "passive"))
    )
    (net (code "86") (name "/SW2A") (class "Default")
      (node (ref "IC8") (pin "7") (pinfunction "D_7") (pintype "bidirectional"))
      (node (ref "R53") (pin "2") (pinfunction "2_2") (pintype "passive"))
    )
    (net (code "87") (name "/SW2B") (class "Default")
      (node (ref "IC8") (pin "10") (pinfunction "D_10") (pintype "bidirectional"))
      (node (ref "R54") (pin "2") (pinfunction "2_2") (pintype "passive"))
    )
    (net (code "88") (name "/SW3A") (class "Default")
      (node (ref "IC9") (pin "2") (pinfunction "D_2") (pintype "bidirectional"))
      (node (ref "R57") (pin "2") (pinfunction "2_2") (pintype "passive"))
    )
    (net (code "89") (name "/SW3B") (class "Default")
      (node (ref "IC9") (pin "15") (pinfunction "D_15") (pintype "bidirectional"))
      (node (ref "R58") (pin "2") (pinfunction "2_2") (pintype "passive"))
    )
    (net (code "90") (name "/SW4A") (class "Default")
      (node (ref "IC9") (pin "7") (pinfunction "D_7") (pintype "bidirectional"))
      (node (ref "R55") (pin "2") (pinfunction "2_2") (pintype "passive"))
    )
    (net (code "91") (name "/SW4B") (class "Default")
      (node (ref "IC9") (pin "10") (pinfunction "D_10") (pintype "bidirectional"))
      (node (ref "R56") (pin "2") (pinfunction "2_2") (pintype "passive"))
    )
    (net (code "92") (name "/SW5A") (class "Default")
      (node (ref "IC10") (pin "2") (pinfunction "D_2") (pintype "bidirectional"))
      (node (ref "R67") (pin "2") (pinfunction "2_2") (pintype "passive"))
    )
    (net (code "93") (name "/SW5B") (class "Default")
      (node (ref "IC10") (pin "15") (pinfunction "D_15") (pintype "bidirectional"))
      (node (ref "R68") (pin "2") (pinfunction "2_2") (pintype "passive"))
    )
    (net (code "94") (name "/SW6A") (class "Default")
      (node (ref "IC10") (pin "7") (pinfunction "D_7") (pintype "bidirectional"))
      (node (ref "R61") (pin "2") (pinfunction "2_2") (pintype "passive"))
    )
    (net (code "95") (name "/SW6B") (class "Default")
      (node (ref "IC10") (pin "10") (pinfunction "D_10") (pintype "bidirectional"))
      (node (ref "R62") (pin "2") (pinfunction "2_2") (pintype "passive"))
    )
    (net (code "96") (name "/SW7A") (class "Default")
      (node (ref "IC11") (pin "2") (pinfunction "D_2") (pintype "bidirectional"))
      (node (ref "R65") (pin "2") (pinfunction "2_2") (pintype "passive"))
    )
    (net (code "97") (name "/SW7B") (class "Default")
      (node (ref "IC11") (pin "15") (pinfunction "D_15") (pintype "bidirectional"))
      (node (ref "R66") (pin "2") (pinfunction "2_2") (pintype "passive"))
    )
    (net (code "98") (name "/SW8A") (class "Default")
      (node (ref "IC11") (pin "7") (pinfunction "D_7") (pintype "bidirectional"))
      (node (ref "R63") (pin "2") (pinfunction "2_2") (pintype "passive"))
    )
    (net (code "99") (name "/SW8B") (class "Default")
      (node (ref "IC11") (pin "10") (pinfunction "D_10") (pintype "bidirectional"))
      (node (ref "R64") (pin "2") (pinfunction "2_2") (pintype "passive"))
    )
    (net (code "100") (name "/VL") (class "Default")
      (node (ref "IC10") (pin "12") (pinfunction "VL_12") (pintype "bidirectional"))
      (node (ref "IC11") (pin "12") (pinfunction "VL_12") (pintype "bidirectional"))
      (node (ref "IC8") (pin "12") (pinfunction "VL_12") (pintype "bidirectional"))
      (node (ref "IC9") (pin "12") (pinfunction "VL_12") (pintype "bidirectional"))
      (node (ref "R77") (pin "2") (pinfunction "2_2") (pintype "passive"))
      (node (ref "R78") (pin "1") (pinfunction "1_1") (pintype "passive"))
    )
    (net (code "101") (name "/~{RST}") (class "Default")
      (node (ref "IC1") (pin "3") (pinfunction "~{RESET}_3") (pintype "bidirectional"))
      (node (ref "R1") (pin "2") (pinfunction "2_2") (pintype "passive"))
    )
    (net (code "102") (name "GND") (class "Default")
      (node (ref "C1") (pin "1") (pinfunction "1_1") (pintype "passive"))
      (node (ref "C10") (pin "2") (pinfunction "2_2") (pintype "passive"))
      (node (ref "C11") (pin "1") (pinfunction "1_1") (pintype "passive"))
      (node (ref "C12") (pin "2") (pinfunction "2_2") (pintype "passive"))
      (node (ref "C13") (pin "1") (pinfunction "1_1") (pintype "passive"))
      (node (ref "C14") (pin "1") (pinfunction "1_1") (pintype "passive"))
      (node (ref "C15") (pin "1") (pinfunction "1_1") (pintype "passive"))
      (node (ref "C16") (pin "1") (pinfunction "1_1") (pintype "passive"))
      (node (ref "C17") (pin "2") (pinfunction "2_2") (pintype "passive"))
      (node (ref "C18") (pin "2") (pinfunction "2_2") (pintype "passive"))
      (node (ref "C19") (pin "1") (pinfunction "1_1") (pintype "passive"))
      (node (ref "C2") (pin "2") (pinfunction "2_2") (pintype "passive"))
      (node (ref "C20") (pin "2") (pinfunction "2_2") (pintype "passive"))
      (node (ref "C21") (pin "1") (pinfunction "1_1") (pintype "passive"))
      (node (ref "C22") (pin "2") (pinfunction "2_2") (pintype "passive"))
      (node (ref "C23") (pin "1") (pinfunction "1_1") (pintype "passive"))
      (node (ref "C28") (pin "1") (pinfunction "1_1") (pintype "passive"))
      (node (ref "C29") (pin "2") (pinfunction "2_2") (pintype "passive"))
      (node (ref "C3") (pin "1") (pinfunction "1_1") (pintype "passive"))
      (node (ref "C30") (pin "1") (pinfunction "1_1") (pintype "passive"))
      (node (ref "C31") (pin "2") (pinfunction "2_2") (pintype "passive"))
      (node (ref "C32") (pin "1") (pinfunction "1_1") (pintype "passive"))
      (node (ref "C4") (pin "2") (pinfunction "2_2") (pintype "passive"))
      (node (ref "C5") (pin "1") (pinfunction "1_1") (pintype "passive"))
      (node (ref "C6") (pin "2") (pinfunction "2_2") (pintype "passive"))
      (node (ref "C7") (pin "1") (pinfunction "1_1") (pintype "passive"))
      (node (ref "C8") (pin "2") (pinfunction "2_2") (pintype "passive"))
      (node (ref "C9") (pin "1") (pinfunction "1_1") (pintype "passive"))
      (node (ref "DA1") (pin "8") (pinfunction "GND_8") (pintype "power_in"))
      (node (ref "DA2") (pin "8") (pinfunction "GND_8") (pintype "power_in"))
      (node (ref "DA3") (pin "8") (pinfunction "GND_8") (pintype "power_in"))
      (node (ref "IC1") (pin "12") (pinfunction "VSS_12") (pintype "power_in"))
      (node (ref "IC1") (pin "2") (pinfunction "A1_2") (pintype "bidirectional"))
      (node (ref "IC1") (pin "21") (pinfunction "A0_21") (pintype "bidirectional"))
      (node (ref "IC10") (pin "5") (pinfunction "AGND_5") (pintype "power_in"))
      (node (ref "IC11") (pin "5") (pinfunction "AGND_5") (pintype "power_in"))
      (node (ref "IC2") (pin "10") (pinfunction "+IN_10") (pintype "input"))
      (node (ref "IC2") (pin "12") (pinfunction "+IN_12") (pintype "input"))
      (node (ref "IC2") (pin "3") (pinfunction "+IN_3") (pintype "input"))
      (node (ref "IC3") (pin "3") (pinfunction "+IN_3") (pintype "input"))
      (node (ref "IC3") (pin "5") (pinfunction "+IN_5") (pintype "input"))
      (node (ref "IC4") (pin "10") (pinfunction "+IN_10") (pintype "input"))
      (node (ref "IC4") (pin "12") (pinfunction "+IN_12") (pintype "input"))
      (node (ref "IC4") (pin "3") (pinfunction "+IN_3") (pintype "input"))
      (node (ref "IC4") (pin "5") (pinfunction "+IN_5") (pintype "input"))
      (node (ref "IC7") (pin "10") (pinfunction "+IN_10") (pintype "input"))
      (node (ref "IC7") (pin "12") (pinfunction "+IN_12") (pintype "input"))
      (node (ref "IC7") (pin "3") (pinfunction "+IN_3") (pintype "input"))
      (node (ref "IC7") (pin "5") (pinfunction "+IN_5") (pintype "input"))
      (node (ref "IC8") (pin "5") (pinfunction "AGND_5") (pintype "power_in"))
      (node (ref "IC9") (pin "5") (pinfunction "AGND_5") (pintype "power_in"))
      (node (ref "R12") (pin "1") (pinfunction "1_1") (pintype "passive"))
      (node (ref "R15") (pin "1") (pinfunction "1_1") (pintype "passive"))
      (node (ref "R18") (pin "1") (pinfunction "1_1") (pintype "passive"))
      (node (ref "R21") (pin "1") (pinfunction "1_1") (pintype "passive"))
      (node (ref "R24") (pin "1") (pinfunction "1_1") (pintype "passive"))
      (node (ref "R27") (pin "1") (pinfunction "1_1") (pintype "passive"))
      (node (ref "R3") (pin "1") (pinfunction "1_1") (pintype "passive"))
      (node (ref "R30") (pin "1") (pinfunction "1_1") (pintype "passive"))
      (node (ref "R33") (pin "1") (pinfunction "1_1") (pintype "passive"))
      (node (ref "R36") (pin "1") (pinfunction "1_1") (pintype "passive"))
      (node (ref "R46") (pin "2") (pinfunction "2_2") (pintype "passive"))
      (node (ref "R47") (pin "2") (pinfunction "2_2") (pintype "passive"))
      (node (ref "R49") (pin "2") (pinfunction "2_2") (pintype "passive"))
      (node (ref "R6") (pin "1") (pinfunction "1_1") (pintype "passive"))
      (node (ref "R73") (pin "1") (pinfunction "1_1") (pintype "passive"))
      (node (ref "R74") (pin "1") (pinfunction "1_1") (pintype "passive"))
      (node (ref "R75") (pin "1") (pinfunction "1_1") (pintype "passive"))
      (node (ref "R76") (pin "1") (pinfunction "1_1") (pintype "passive"))
      (node (ref "R78") (pin "2") (pinfunction "2_2") (pintype "passive"))
      (node (ref "R9") (pin "1") (pinfunction "1_1") (pintype "passive"))
      (node (ref "U$2") (pin "7") (pinfunction "7_7") (pintype "passive"))
      (node (ref "U$3") (pin "4") (pinfunction "4_4") (pintype "passive"))
    )
    (net (code "103") (name "Net-(C13-Pad2)") (class "Default")
      (node (ref "C13") (pin "2") (pinfunction "2_2") (pintype "passive"))
      (node (ref "R38") (pin "1") (pinfunction "1_1") (pintype "passive"))
    )
    (net (code "104") (name "Net-(C14-Pad2)") (class "Default")
      (node (ref "C14") (pin "2") (pinfunction "2_2") (pintype "passive"))
      (node (ref "R39") (pin "1") (pinfunction "1_1") (pintype "passive"))
    )
    (net (code "105") (name "Net-(C15-Pad2)") (class "Default")
      (node (ref "C15") (pin "2") (pinfunction "2_2") (pintype "passive"))
      (node (ref "R40") (pin "1") (pinfunction "1_1") (pintype "passive"))
    )
    (net (code "106") (name "Net-(DA1B-CV2)") (class "Default")
      (node (ref "DA1") (pin "6") (pinfunction "CV2_6") (pintype "input"))
      (node (ref "R29") (pin "2") (pinfunction "2_2") (pintype "passive"))
      (node (ref "R30") (pin "2") (pinfunction "2_2") (pintype "passive"))
    )
    (net (code "107") (name "Net-(DA1B-CV3)") (class "Default")
      (node (ref "DA1") (pin "11") (pinfunction "CV3_11") (pintype "input"))
      (node (ref "R32") (pin "2") (pinfunction "2_2") (pintype "passive"))
      (node (ref "R33") (pin "2") (pinfunction "2_2") (pintype "passive"))
    )
    (net (code "108") (name "Net-(DA1B-CV4)") (class "Default")
      (node (ref "DA1") (pin "14") (pinfunction "CV4_14") (pintype "input"))
      (node (ref "R35") (pin "2") (pinfunction "2_2") (pintype "passive"))
      (node (ref "R36") (pin "2") (pinfunction "2_2") (pintype "passive"))
    )
    (net (code "109") (name "Net-(DA1B-OUT1)") (class "Default")
      (node (ref "DA1") (pin "4") (pinfunction "OUT1_4") (pintype "output"))
      (node (ref "IC7") (pin "13") (pinfunction "-IN_13") (pintype "input"))
      (node (ref "R51") (pin "2") (pinfunction "2_2") (pintype "passive"))
    )
    (net (code "110") (name "Net-(DA1B-OUT2)") (class "Default")
      (node (ref "DA1") (pin "5") (pinfunction "OUT2_5") (pintype "output"))
      (node (ref "IC2") (pin "9") (pinfunction "-IN_9") (pintype "input"))
      (node (ref "R50") (pin "2") (pinfunction "2_2") (pintype "passive"))
      (node (ref "R69") (pin "1") (pinfunction "1_1") (pintype "passive"))
      (node (ref "R71") (pin "1") (pinfunction "1_1") (pintype "passive"))
    )
    (net (code "111") (name "Net-(DA1B-OUT3)") (class "Default")
      (node (ref "DA1") (pin "12") (pinfunction "OUT3_12") (pintype "output"))
      (node (ref "IC2") (pin "6") (pinfunction "-IN_6") (pintype "input"))
      (node (ref "R52") (pin "2") (pinfunction "2_2") (pintype "passive"))
    )
    (net (code "112") (name "Net-(DA1B-OUT4)") (class "Default")
      (node (ref "DA1") (pin "13") (pinfunction "OUT4_13") (pintype "output"))
      (node (ref "IC2") (pin "5") (pinfunction "+IN_5") (pintype "input"))
      (node (ref "R49") (pin "1") (pinfunction "1_1") (pintype "passive"))
    )
    (net (code "113") (name "Net-(DA1B-VREF)") (class "Default")
      (node (ref "DA1") (pin "1") (pinfunction "VREF_1") (pintype "output"))
      (node (ref "R40") (pin "2") (pinfunction "2_2") (pintype "passive"))
    )
    (net (code "114") (name "Net-(DA2B-CV2)") (class "Default")
      (node (ref "DA2") (pin "6") (pinfunction "CV2_6") (pintype "input"))
      (node (ref "R5") (pin "2") (pinfunction "2_2") (pintype "passive"))
      (node (ref "R6") (pin "2") (pinfunction "2_2") (pintype "passive"))
    )
    (net (code "115") (name "Net-(DA2B-CV3)") (class "Default")
      (node (ref "DA2") (pin "11") (pinfunction "CV3_11") (pintype "input"))
      (node (ref "R8") (pin "2") (pinfunction "2_2") (pintype "passive"))
      (node (ref "R9") (pin "2") (pinfunction "2_2") (pintype "passive"))
    )
    (net (code "116") (name "Net-(DA2B-CV4)") (class "Default")
      (node (ref "DA2") (pin "14") (pinfunction "CV4_14") (pintype "input"))
      (node (ref "R11") (pin "2") (pinfunction "2_2") (pintype "passive"))
      (node (ref "R12") (pin "2") (pinfunction "2_2") (pintype "passive"))
    )
    (net (code "117") (name "Net-(DA2B-VREF)") (class "Default")
      (node (ref "DA2") (pin "1") (pinfunction "VREF_1") (pintype "output"))
      (node (ref "R38") (pin "2") (pinfunction "2_2") (pintype "passive"))
    )
    (net (code "118") (name "Net-(DA3B-CV2)") (class "Default")
      (node (ref "DA3") (pin "6") (pinfunction "CV2_6") (pintype "input"))
      (node (ref "R17") (pin "2") (pinfunction "2_2") (pintype "passive"))
      (node (ref "R18") (pin "2") (pinfunction "2_2") (pintype "passive"))
    )
    (net (code "119") (name "Net-(DA3B-CV3)") (class "Default")
      (node (ref "DA3") (pin "11") (pinfunction "CV3_11") (pintype "input"))
      (node (ref "R20") (pin "2") (pinfunction "2_2") (pintype "passive"))
      (node (ref "R21") (pin "2") (pinfunction "2_2") (pintype "passive"))
    )
    (net (code "120") (name "Net-(DA3B-CV4)") (class "Default")
      (node (ref "DA3") (pin "14") (pinfunction "CV4_14") (pintype "input"))
      (node (ref "R23") (pin "2") (pinfunction "2_2") (pintype "passive"))
      (node (ref "R24") (pin "2") (pinfunction "2_2") (pintype "passive"))
    )
    (net (code "121") (name "Net-(DA3B-OUT2)") (class "Default")
      (node (ref "DA3") (pin "5") (pinfunction "OUT2_5") (pintype "output"))
      (node (ref "IC6") (pin "3") (pinfunction "+IN_3") (pintype "input"))
      (node (ref "R46") (pin "1") (pinfunction "1_1") (pintype "passive"))
    )
    (net (code "122") (name "Net-(DA3B-VREF)") (class "Default")
      (node (ref "DA3") (pin "1") (pinfunction "VREF_1") (pintype "output"))
      (node (ref "R39") (pin "2") (pinfunction "2_2") (pintype "passive"))
    )
    (net (code "123") (name "Net-(IC1-IO0_0)") (class "Default")
      (node (ref "IC1") (pin "4") (pinfunction "IO0_0_4") (pintype "bidirectional"))
      (node (ref "R72") (pin "1") (pinfunction "1_1") (pintype "passive"))
    )
    (net (code "124") (name "Net-(IC1-IO0_1)") (class "Default")
      (node (ref "IC1") (pin "5") (pinfunction "IO0_1_5") (pintype "bidirectional"))
      (node (ref "R83") (pin "1") (pinfunction "1_1") (pintype "passive"))
    )
    (net (code "125") (name "Net-(IC1-IO0_2)") (class "Default")
      (node (ref "IC1") (pin "6") (pinfunction "IO0_2_6") (pintype "bidirectional"))
      (node (ref "R84") (pin "1") (pinfunction "1_1") (pintype "passive"))
    )
    (net (code "126") (name "Net-(IC1-IO0_3)") (class "Default")
      (node (ref "IC1") (pin "7") (pinfunction "IO0_3_7") (pintype "bidirectional"))
      (node (ref "R85") (pin "1") (pinfunction "1_1") (pintype "passive"))
    )
    (net (code "127") (name "Net-(IC1-IO0_4)") (class "Default")
      (node (ref "IC1") (pin "8") (pinfunction "IO0_4_8") (pintype "bidirectional"))
      (node (ref "R86") (pin "1") (pinfunction "1_1") (pintype "passive"))
    )
    (net (code "128") (name "Net-(IC1-IO0_5)") (class "Default")
      (node (ref "IC1") (pin "9") (pinfunction "IO0_5_9") (pintype "bidirectional"))
      (node (ref "R87") (pin "1") (pinfunction "1_1") (pintype "passive"))
    )
    (net (code "129") (name "Net-(IC1-IO0_6)") (class "Default")
      (node (ref "IC1") (pin "10") (pinfunction "IO0_6_10") (pintype "bidirectional"))
      (node (ref "R88") (pin "1") (pinfunction "1_1") (pintype "passive"))
    )
    (net (code "130") (name "Net-(IC1-IO0_7)") (class "Default")
      (node (ref "IC1") (pin "11") (pinfunction "IO0_7_11") (pintype "bidirectional"))
      (node (ref "R89") (pin "1") (pinfunction "1_1") (pintype "passive"))
    )
    (net (code "131") (name "Net-(IC1-IO1_0)") (class "Default")
      (node (ref "IC1") (pin "13") (pinfunction "IO1_0_13") (pintype "bidirectional"))
      (node (ref "R90") (pin "1") (pinfunction "1_1") (pintype "passive"))
    )
    (net (code "132") (name "Net-(IC1-IO1_1)") (class "Default")
      (node (ref "IC1") (pin "14") (pinfunction "IO1_1_14") (pintype "bidirectional"))
      (node (ref "R91") (pin "1") (pinfunction "1_1") (pintype "passive"))
    )
    (net (code "133") (name "Net-(IC1-IO1_2)") (class "Default")
      (node (ref "IC1") (pin "15") (pinfunction "IO1_2_15") (pintype "bidirectional"))
      (node (ref "R92") (pin "1") (pinfunction "1_1") (pintype "passive"))
    )
    (net (code "134") (name "Net-(IC1-IO1_3)") (class "Default")
      (node (ref "IC1") (pin "16") (pinfunction "IO1_3_16") (pintype "bidirectional"))
      (node (ref "R93") (pin "1") (pinfunction "1_1") (pintype "passive"))
    )
    (net (code "135") (name "Net-(IC1-IO1_4)") (class "Default")
      (node (ref "IC1") (pin "17") (pinfunction "IO1_4_17") (pintype "bidirectional"))
      (node (ref "R94") (pin "1") (pinfunction "1_1") (pintype "passive"))
    )
    (net (code "136") (name "Net-(IC1-IO1_5)") (class "Default")
      (node (ref "IC1") (pin "18") (pinfunction "IO1_5_18") (pintype "bidirectional"))
      (node (ref "R95") (pin "1") (pinfunction "1_1") (pintype "passive"))
    )
    (net (code "137") (name "Net-(IC1-IO1_6)") (class "Default")
      (node (ref "IC1") (pin "19") (pinfunction "IO1_6_19") (pintype "bidirectional"))
      (node (ref "R96") (pin "1") (pinfunction "1_1") (pintype "passive"))
    )
    (net (code "138") (name "Net-(IC1-IO1_7)") (class "Default")
      (node (ref "IC1") (pin "20") (pinfunction "IO1_7_20") (pintype "bidirectional"))
      (node (ref "R97") (pin "1") (pinfunction "1_1") (pintype "passive"))
    )
    (net (code "139") (name "Net-(IC7A--IN)") (class "Default")
      (node (ref "IC7") (pin "2") (pinfunction "-IN_2") (pintype "input"))
      (node (ref "R98") (pin "2") (pinfunction "2_2") (pintype "passive"))
      (node (ref "R99") (pin "1") (pinfunction "1_1") (pintype "passive"))
    )
    (net (code "140") (name "Net-(IC7A-OUT)") (class "Default")
      (node (ref "IC7") (pin "1") (pinfunction "OUT_1") (pintype "output"))
      (node (ref "JP4") (pin "1") (pinfunction "1_1") (pintype "passive"))
      (node (ref "R98") (pin "1") (pinfunction "1_1") (pintype "passive"))
    )
    (net (code "141") (name "Net-(IC7D-OUT)") (class "Default")
      (node (ref "IC7") (pin "14") (pinfunction "OUT_14") (pintype "output"))
      (node (ref "R51") (pin "1") (pinfunction "1_1") (pintype "passive"))
      (node (ref "R71") (pin "2") (pinfunction "2_2") (pintype "passive"))
    )
    (net (code "142") (name "unconnected-(IC1-~{INT}-Pad1)") (class "Default")
      (node (ref "IC1") (pin "1") (pinfunction "~{INT}_1") (pintype "bidirectional"))
    )
  )
)
